# lcdRGB.net
KiCad netlist of a schematic drawn in Altium Designer
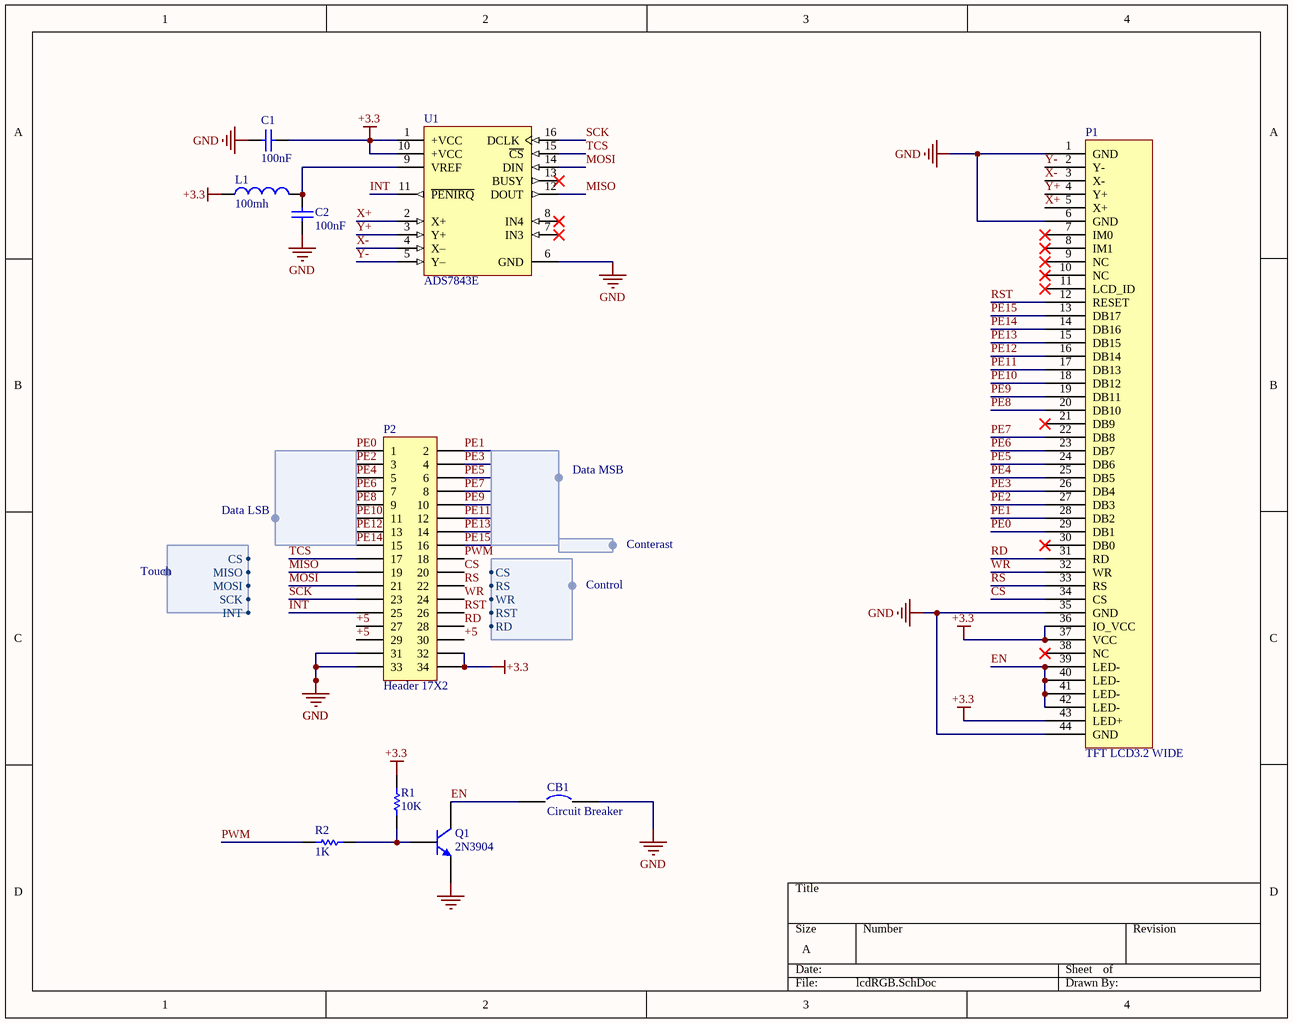
[diagram p0: lcdRGB.SchDoc]

(export (version "E")
  (design (tool "Eeschema 10.0.6"))
  (components
    (comp (ref "C1")
      (value "100nF")
      (footprint "1206")
      (description "Capacitor")
      (fields (field (name "PUBLISHER") "Altium Limited"))
      (libsource (lib "Miscellaneous Devices") (part "Cap"))
    )
    (comp (ref "C2")
      (value "100nF")
      (footprint "1206")
      (description "Capacitor")
      (fields (field (name "PUBLISHER") "Altium Limited"))
      (libsource (lib "Miscellaneous Devices") (part "Cap"))
    )
    (comp (ref "CB1")
      (value "Circuit Breaker")
      (footprint "0603c")
      (fields (field (name "PUBLISHER") "Altium Limited"))
      (libsource (lib "Miscellaneous Devices") (part "Circuit Breaker"))
    )
    (comp (ref "L1")
      (value "100mh")
      (footprint "1206")
      (description "Inductor")
      (fields (field (name "PUBLISHER") "Altium Limited"))
      (libsource (lib "Miscellaneous Devices") (part "Inductor"))
    )
    (comp (ref "P1")
      (value "TFT LCD3.2 WIDE")
      (footprint "FPC44")
      (libsource (lib "Schlib1") (part "TFTLCD3.2"))
    )
    (comp (ref "P2")
      (value "Header 17X2")
      (footprint "IDC34S")
      (description "Header, 17-Pin, Dual row")
      (fields (field (name "PUBLISHER") "Altium Limited"))
      (libsource (lib "Miscellaneous Connectors") (part "Header 17X2"))
    )
    (comp (ref "Q1")
      (value "2N3904")
      (footprint "BCY-W3/E4")
      (description "NPN General Purpose Amplifier")
      (fields (field (name "PUBLISHER") "Altium Limited"))
      (libsource (lib "Miscellaneous Devices") (part "2N3904"))
    )
    (comp (ref "R1")
      (value "10K")
      (footprint "1206")
      (description "Semiconductor Resistor")
      (fields (field (name "PUBLISHER") "Altium Limited"))
      (libsource (lib "*") (part "Res Semi"))
    )
    (comp (ref "R2")
      (value "1K")
      (footprint "1206")
      (description "Semiconductor Resistor")
      (fields (field (name "PUBLISHER") "Altium Limited"))
      (libsource (lib "*") (part "Res Semi"))
    )
    (comp (ref "U1")
      (value "ADS7843E")
      (footprint "DBQ016")
      (description "4-Wire Touch Screen Controller, 16-Pin SSOP, Pb-Free")
      (fields (field (name "PUBLISHER") "Altium Limited"))
      (libsource (lib "TI Interface Touch Screen Controller") (part "ADS7843E"))
    )
  )
  (nets
    (net (code "1") (name "+3.3") (class "Default")
      (node (ref "C1") (pin "2") (pinfunction "2_2") (pintype "passive"))
      (node (ref "L1") (pin "1") (pinfunction "1_1") (pintype "passive"))
      (node (ref "P1") (pin "36") (pinfunction "IO_VCC_36") (pintype "passive"))
      (node (ref "P1") (pin "37") (pinfunction "VCC_37") (pintype "passive"))
      (node (ref "P1") (pin "43") (pinfunction "LED+_43") (pintype "passive"))
      (node (ref "P2") (pin "32") (pinfunction "32_32") (pintype "passive"))
      (node (ref "P2") (pin "34") (pinfunction "34_34") (pintype "passive"))
      (node (ref "R1") (pin "2") (pinfunction "2_2") (pintype "passive"))
      (node (ref "U1") (pin "1") (pinfunction "+VCC_1") (pintype "power_in"))
      (node (ref "U1") (pin "10") (pinfunction "+VCC_10") (pintype "power_in"))
    )
    (net (code "2") (name "/+5") (class "Default")
      (node (ref "P2") (pin "27") (pinfunction "27_27") (pintype "passive"))
      (node (ref "P2") (pin "29") (pinfunction "29_29") (pintype "passive"))
      (node (ref "P2") (pin "30") (pinfunction "30_30") (pintype "passive"))
    )
    (net (code "3") (name "/CS") (class "Default")
      (node (ref "P1") (pin "34") (pinfunction "CS_34") (pintype "passive"))
      (node (ref "P2") (pin "20") (pinfunction "20_20") (pintype "passive"))
    )
    (net (code "4") (name "/EN") (class "Default")
      (node (ref "CB1") (pin "1") (pinfunction "1_1") (pintype "passive"))
      (node (ref "P1") (pin "39") (pinfunction "LED-_39") (pintype "passive"))
      (node (ref "P1") (pin "40") (pinfunction "LED-_40") (pintype "passive"))
      (node (ref "P1") (pin "41") (pinfunction "LED-_41") (pintype "passive"))
      (node (ref "P1") (pin "42") (pinfunction "LED-_42") (pintype "passive"))
      (node (ref "Q1") (pin "3") (pinfunction "C_3") (pintype "passive"))
    )
    (net (code "5") (name "/INT") (class "Default")
      (node (ref "P2") (pin "25") (pinfunction "25_25") (pintype "passive"))
      (node (ref "U1") (pin "11") (pinfunction "~{PENIRQ}_11") (pintype "output"))
    )
    (net (code "6") (name "/MISO") (class "Default")
      (node (ref "P2") (pin "19") (pinfunction "19_19") (pintype "passive"))
      (node (ref "U1") (pin "12") (pinfunction "DOUT_12") (pintype "output"))
    )
    (net (code "7") (name "/MOSI") (class "Default")
      (node (ref "P2") (pin "21") (pinfunction "21_21") (pintype "passive"))
      (node (ref "U1") (pin "14") (pinfunction "DIN_14") (pintype "input"))
    )
    (net (code "8") (name "/PE0") (class "Default")
      (node (ref "P1") (pin "29") (pinfunction "DB1_29") (pintype "passive"))
      (node (ref "P2") (pin "1") (pinfunction "1_1") (pintype "passive"))
    )
    (net (code "9") (name "/PE1") (class "Default")
      (node (ref "P1") (pin "28") (pinfunction "DB2_28") (pintype "passive"))
      (node (ref "P2") (pin "2") (pinfunction "2_2") (pintype "passive"))
    )
    (net (code "10") (name "/PE2") (class "Default")
      (node (ref "P1") (pin "27") (pinfunction "DB3_27") (pintype "passive"))
      (node (ref "P2") (pin "3") (pinfunction "3_3") (pintype "passive"))
    )
    (net (code "11") (name "/PE3") (class "Default")
      (node (ref "P1") (pin "26") (pinfunction "DB4_26") (pintype "passive"))
      (node (ref "P2") (pin "4") (pinfunction "4_4") (pintype "passive"))
    )
    (net (code "12") (name "/PE4") (class "Default")
      (node (ref "P1") (pin "25") (pinfunction "DB5_25") (pintype "passive"))
      (node (ref "P2") (pin "5") (pinfunction "5_5") (pintype "passive"))
    )
    (net (code "13") (name "/PE5") (class "Default")
      (node (ref "P1") (pin "24") (pinfunction "DB6_24") (pintype "passive"))
      (node (ref "P2") (pin "6") (pinfunction "6_6") (pintype "passive"))
    )
    (net (code "14") (name "/PE6") (class "Default")
      (node (ref "P1") (pin "23") (pinfunction "DB7_23") (pintype "passive"))
      (node (ref "P2") (pin "7") (pinfunction "7_7") (pintype "passive"))
    )
    (net (code "15") (name "/PE7") (class "Default")
      (node (ref "P1") (pin "22") (pinfunction "DB8_22") (pintype "passive"))
      (node (ref "P2") (pin "8") (pinfunction "8_8") (pintype "passive"))
    )
    (net (code "16") (name "/PE8") (class "Default")
      (node (ref "P1") (pin "20") (pinfunction "DB10_20") (pintype "passive"))
      (node (ref "P2") (pin "9") (pinfunction "9_9") (pintype "passive"))
    )
    (net (code "17") (name "/PE9") (class "Default")
      (node (ref "P1") (pin "19") (pinfunction "DB11_19") (pintype "passive"))
      (node (ref "P2") (pin "10") (pinfunction "10_10") (pintype "passive"))
    )
    (net (code "18") (name "/PE10") (class "Default")
      (node (ref "P1") (pin "18") (pinfunction "DB12_18") (pintype "passive"))
      (node (ref "P2") (pin "11") (pinfunction "11_11") (pintype "passive"))
    )
    (net (code "19") (name "/PE11") (class "Default")
      (node (ref "P1") (pin "17") (pinfunction "DB13_17") (pintype "passive"))
      (node (ref "P2") (pin "12") (pinfunction "12_12") (pintype "passive"))
    )
    (net (code "20") (name "/PE12") (class "Default")
      (node (ref "P1") (pin "16") (pinfunction "DB14_16") (pintype "passive"))
      (node (ref "P2") (pin "13") (pinfunction "13_13") (pintype "passive"))
    )
    (net (code "21") (name "/PE13") (class "Default")
      (node (ref "P1") (pin "15") (pinfunction "DB15_15") (pintype "passive"))
      (node (ref "P2") (pin "14") (pinfunction "14_14") (pintype "passive"))
    )
    (net (code "22") (name "/PE14") (class "Default")
      (node (ref "P1") (pin "14") (pinfunction "DB16_14") (pintype "passive"))
      (node (ref "P2") (pin "15") (pinfunction "15_15") (pintype "passive"))
    )
    (net (code "23") (name "/PE15") (class "Default")
      (node (ref "P1") (pin "13") (pinfunction "DB17_13") (pintype "passive"))
      (node (ref "P2") (pin "16") (pinfunction "16_16") (pintype "passive"))
    )
    (net (code "24") (name "/PWM") (class "Default")
      (node (ref "P2") (pin "18") (pinfunction "18_18") (pintype "passive"))
      (node (ref "R2") (pin "2") (pinfunction "2_2") (pintype "passive"))
    )
    (net (code "25") (name "/RD") (class "Default")
      (node (ref "P1") (pin "31") (pinfunction "RD_31") (pintype "passive"))
      (node (ref "P2") (pin "28") (pinfunction "28_28") (pintype "passive"))
    )
    (net (code "26") (name "/RS") (class "Default")
      (node (ref "P1") (pin "33") (pinfunction "RS_33") (pintype "passive"))
      (node (ref "P2") (pin "22") (pinfunction "22_22") (pintype "passive"))
    )
    (net (code "27") (name "/RST") (class "Default")
      (node (ref "P1") (pin "12") (pinfunction "RESET_12") (pintype "passive"))
      (node (ref "P2") (pin "26") (pinfunction "26_26") (pintype "passive"))
    )
    (net (code "28") (name "/SCK") (class "Default")
      (node (ref "P2") (pin "23") (pinfunction "23_23") (pintype "passive"))
      (node (ref "U1") (pin "16") (pinfunction "DCLK_16") (pintype "input"))
    )
    (net (code "29") (name "/TCS") (class "Default")
      (node (ref "P2") (pin "17") (pinfunction "17_17") (pintype "passive"))
      (node (ref "U1") (pin "15") (pinfunction "~{CS}_15") (pintype "input"))
    )
    (net (code "30") (name "/WR") (class "Default")
      (node (ref "P1") (pin "32") (pinfunction "WR_32") (pintype "passive"))
      (node (ref "P2") (pin "24") (pinfunction "24_24") (pintype "passive"))
    )
    (net (code "31") (name "/X+") (class "Default")
      (node (ref "P1") (pin "5") (pinfunction "X+_5") (pintype "passive"))
      (node (ref "U1") (pin "2") (pinfunction "X+_2") (pintype "input"))
    )
    (net (code "32") (name "/X-") (class "Default")
      (node (ref "P1") (pin "3") (pinfunction "X-_3") (pintype "passive"))
      (node (ref "U1") (pin "4") (pinfunction "X_4") (pintype "input"))
    )
    (net (code "33") (name "/Y+") (class "Default")
      (node (ref "P1") (pin "4") (pinfunction "Y+_4") (pintype "passive"))
      (node (ref "U1") (pin "3") (pinfunction "Y+_3") (pintype "input"))
    )
    (net (code "34") (name "/Y-") (class "Default")
      (node (ref "P1") (pin "2") (pinfunction "Y-_2") (pintype "passive"))
      (node (ref "U1") (pin "5") (pinfunction "Y_5") (pintype "input"))
    )
    (net (code "35") (name "GND") (class "Default")
      (node (ref "C1") (pin "1") (pinfunction "1_1") (pintype "passive"))
      (node (ref "C2") (pin "1") (pinfunction "1_1") (pintype "passive"))
      (node (ref "CB1") (pin "2") (pinfunction "2_2") (pintype "passive"))
      (node (ref "P1") (pin "1") (pinfunction "GND_1") (pintype "passive"))
      (node (ref "P1") (pin "35") (pinfunction "GND_35") (pintype "passive"))
      (node (ref "P1") (pin "44") (pinfunction "GND_44") (pintype "passive"))
      (node (ref "P1") (pin "6") (pinfunction "GND_6") (pintype "passive"))
      (node (ref "P2") (pin "31") (pinfunction "31_31") (pintype "passive"))
      (node (ref "P2") (pin "33") (pinfunction "33_33") (pintype "passive"))
      (node (ref "Q1") (pin "1") (pinfunction "E_1") (pintype "passive"))
      (node (ref "U1") (pin "6") (pinfunction "GND_6") (pintype "power_in"))
    )
    (net (code "36") (name "Net-(Q1-B)") (class "Default")
      (node (ref "Q1") (pin "2") (pinfunction "B_2") (pintype "passive"))
      (node (ref "R1") (pin "1") (pinfunction "1_1") (pintype "passive"))
      (node (ref "R2") (pin "1") (pinfunction "1_1") (pintype "passive"))
    )
    (net (code "37") (name "Net-(U1-VREF)") (class "Default")
      (node (ref "C2") (pin "2") (pinfunction "2_2") (pintype "passive"))
      (node (ref "L1") (pin "2") (pinfunction "2_2") (pintype "passive"))
      (node (ref "U1") (pin "9") (pinfunction "VREF_9") (pintype "power_in"))
    )
    (net (code "38") (name "unconnected-(P1-DB0-Pad30)") (class "Default")
      (node (ref "P1") (pin "30") (pinfunction "DB0_30") (pintype "passive+no_connect"))
    )
    (net (code "39") (name "unconnected-(P1-DB9-Pad21)") (class "Default")
      (node (ref "P1") (pin "21") (pinfunction "DB9_21") (pintype "passive+no_connect"))
    )
    (net (code "40") (name "unconnected-(P1-IM0-Pad7)") (class "Default")
      (node (ref "P1") (pin "7") (pinfunction "IM0_7") (pintype "passive+no_connect"))
    )
    (net (code "41") (name "unconnected-(P1-IM1-Pad8)") (class "Default")
      (node (ref "P1") (pin "8") (pinfunction "IM1_8") (pintype "passive+no_connect"))
    )
    (net (code "42") (name "unconnected-(P1-LCD_ID-Pad11)") (class "Default")
      (node (ref "P1") (pin "11") (pinfunction "LCD_ID_11") (pintype "passive+no_connect"))
    )
    (net (code "43") (name "unconnected-(P1-NC-Pad9)") (class "Default")
      (node (ref "P1") (pin "9") (pinfunction "NC_9") (pintype "passive+no_connect"))
    )
    (net (code "44") (name "unconnected-(P1-NC-Pad10)") (class "Default")
      (node (ref "P1") (pin "10") (pinfunction "NC_10") (pintype "passive+no_connect"))
    )
    (net (code "45") (name "unconnected-(P1-NC-Pad38)") (class "Default")
      (node (ref "P1") (pin "38") (pinfunction "NC_38") (pintype "passive+no_connect"))
    )
    (net (code "46") (name "unconnected-(U1-BUSY-Pad13)") (class "Default")
      (node (ref "U1") (pin "13") (pinfunction "BUSY_13") (pintype "output+no_connect"))
    )
    (net (code "47") (name "unconnected-(U1-IN3-Pad7)") (class "Default")
      (node (ref "U1") (pin "7") (pinfunction "IN3_7") (pintype "input+no_connect"))
    )
    (net (code "48") (name "unconnected-(U1-IN4-Pad8)") (class "Default")
      (node (ref "U1") (pin "8") (pinfunction "IN4_8") (pintype "input+no_connect"))
    )
  )
)
